# control_avr.net
KiCad netlist of a schematic drawn in EAGLE
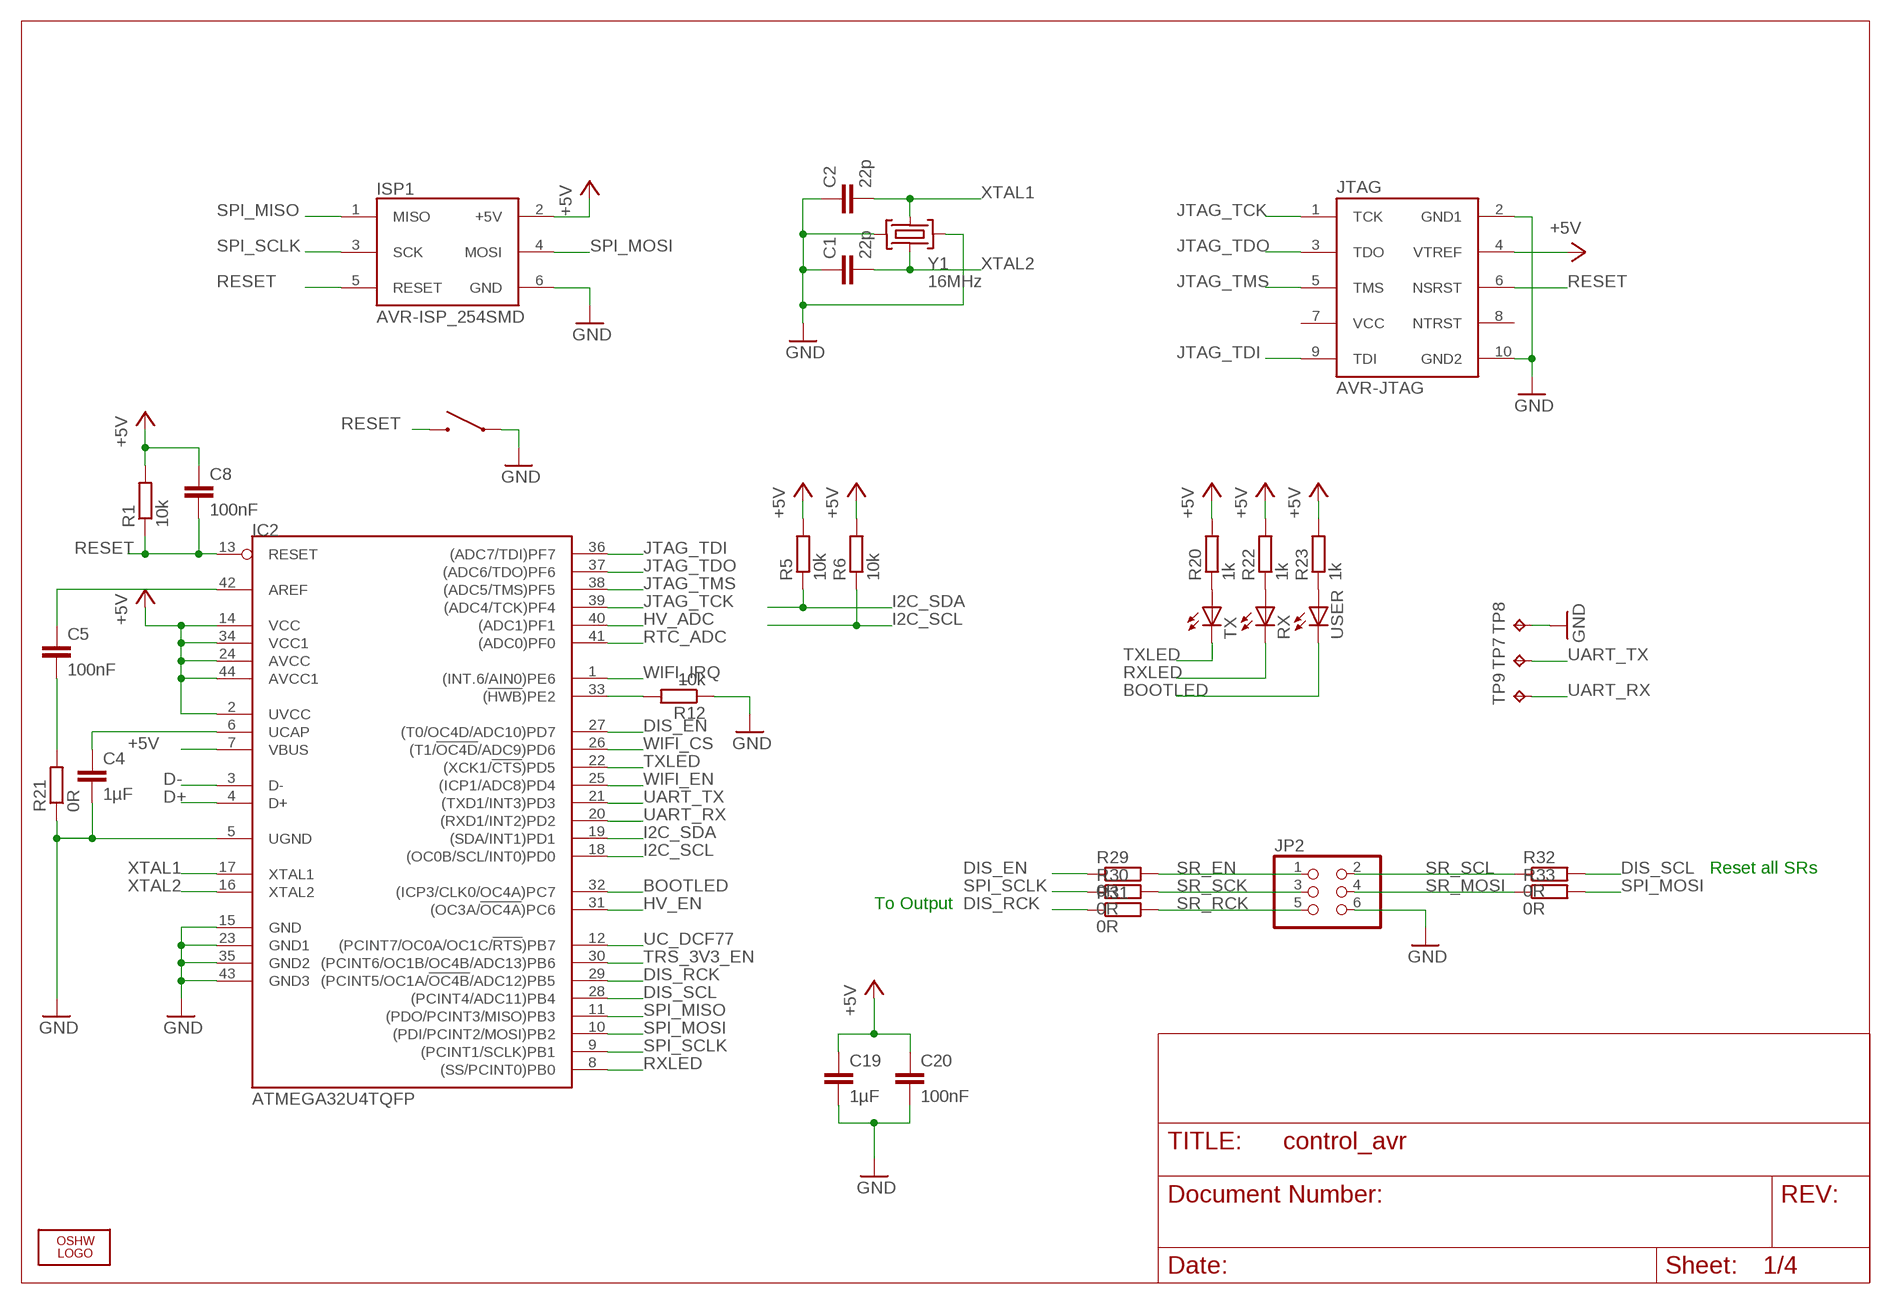
[diagram p0: schematic, sheet 1]
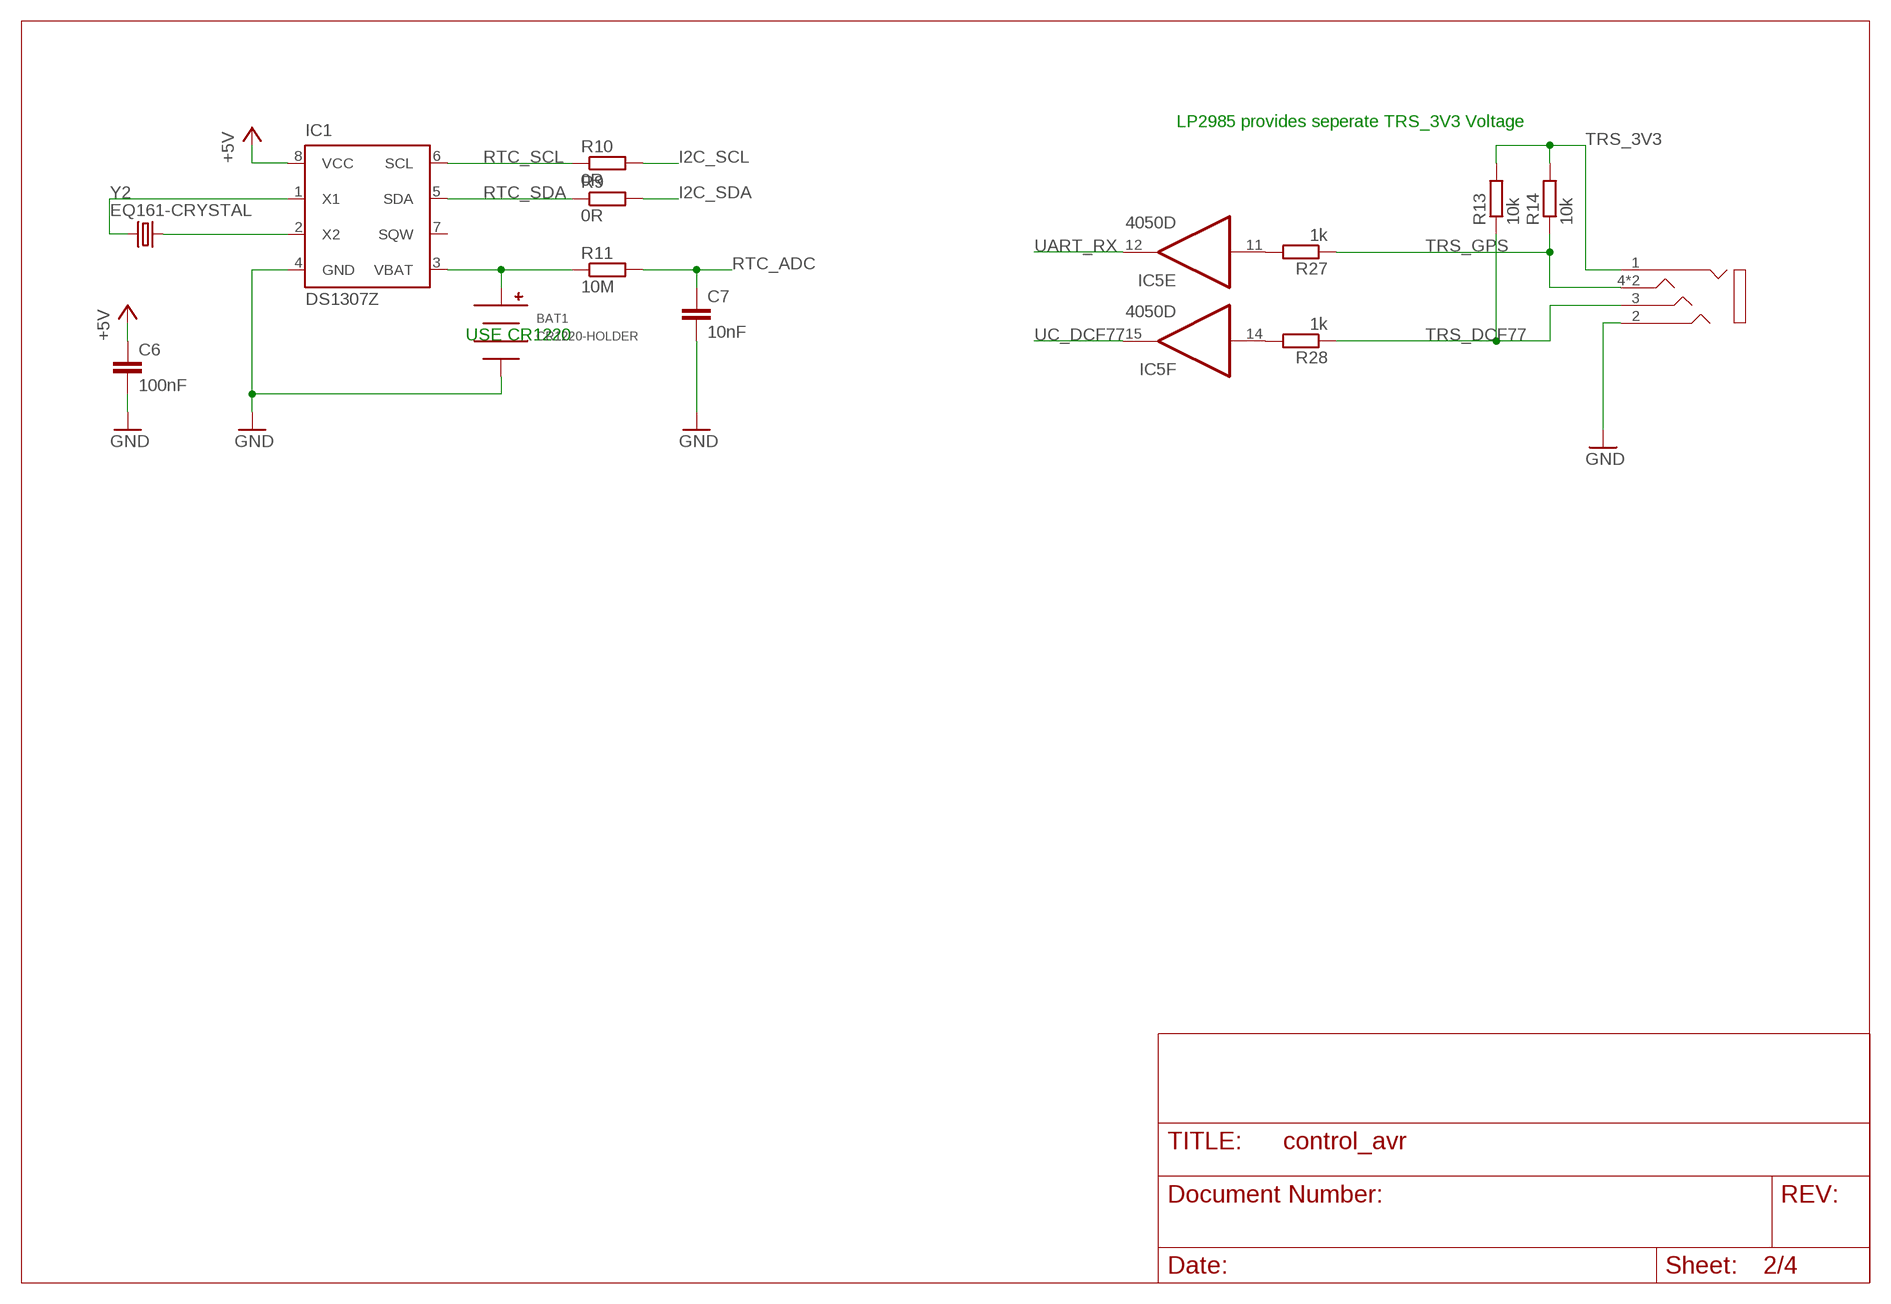
[diagram p1: schematic, sheet 2]
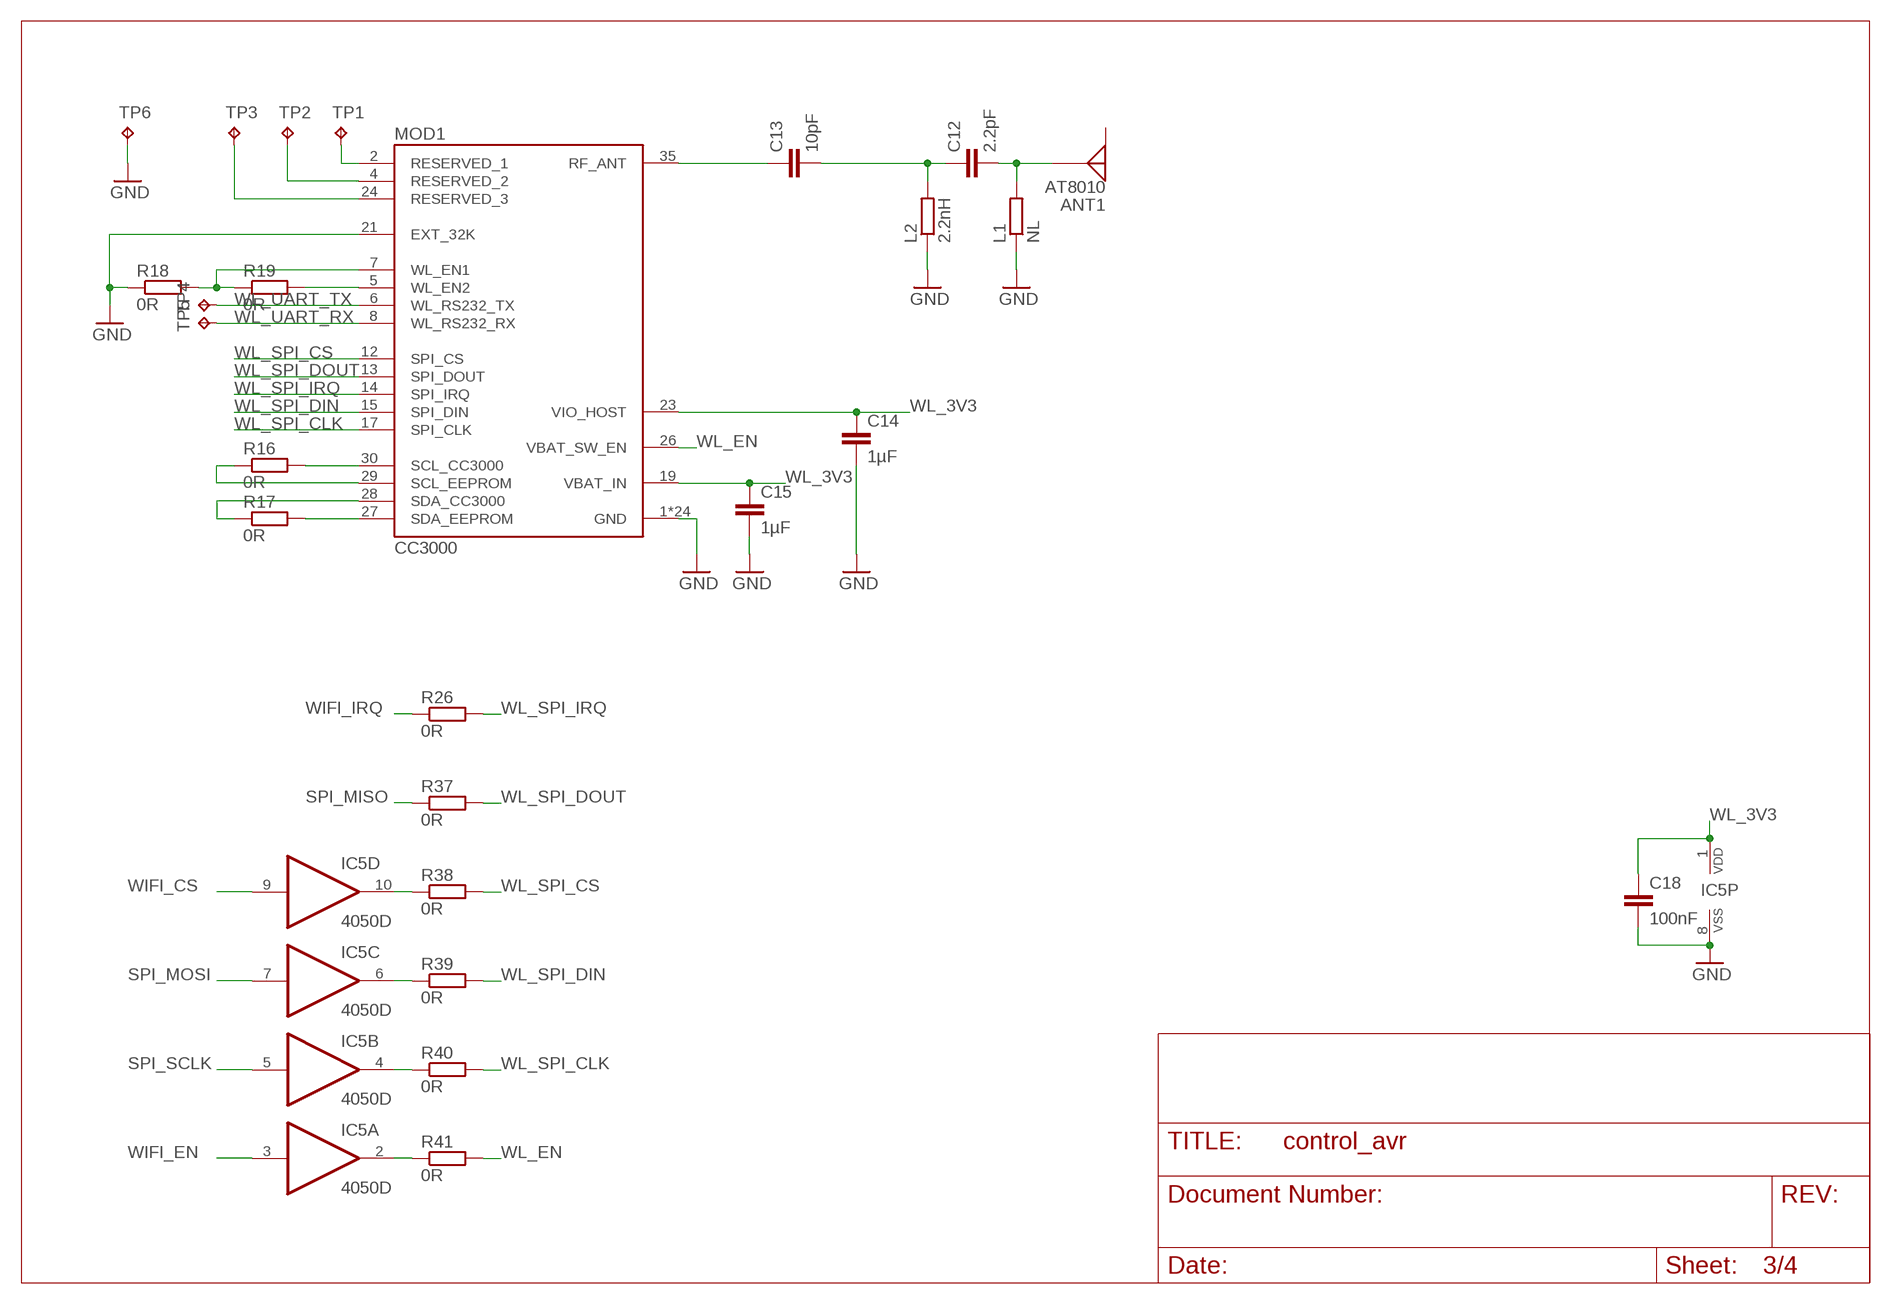
[diagram p2: schematic, sheet 3]
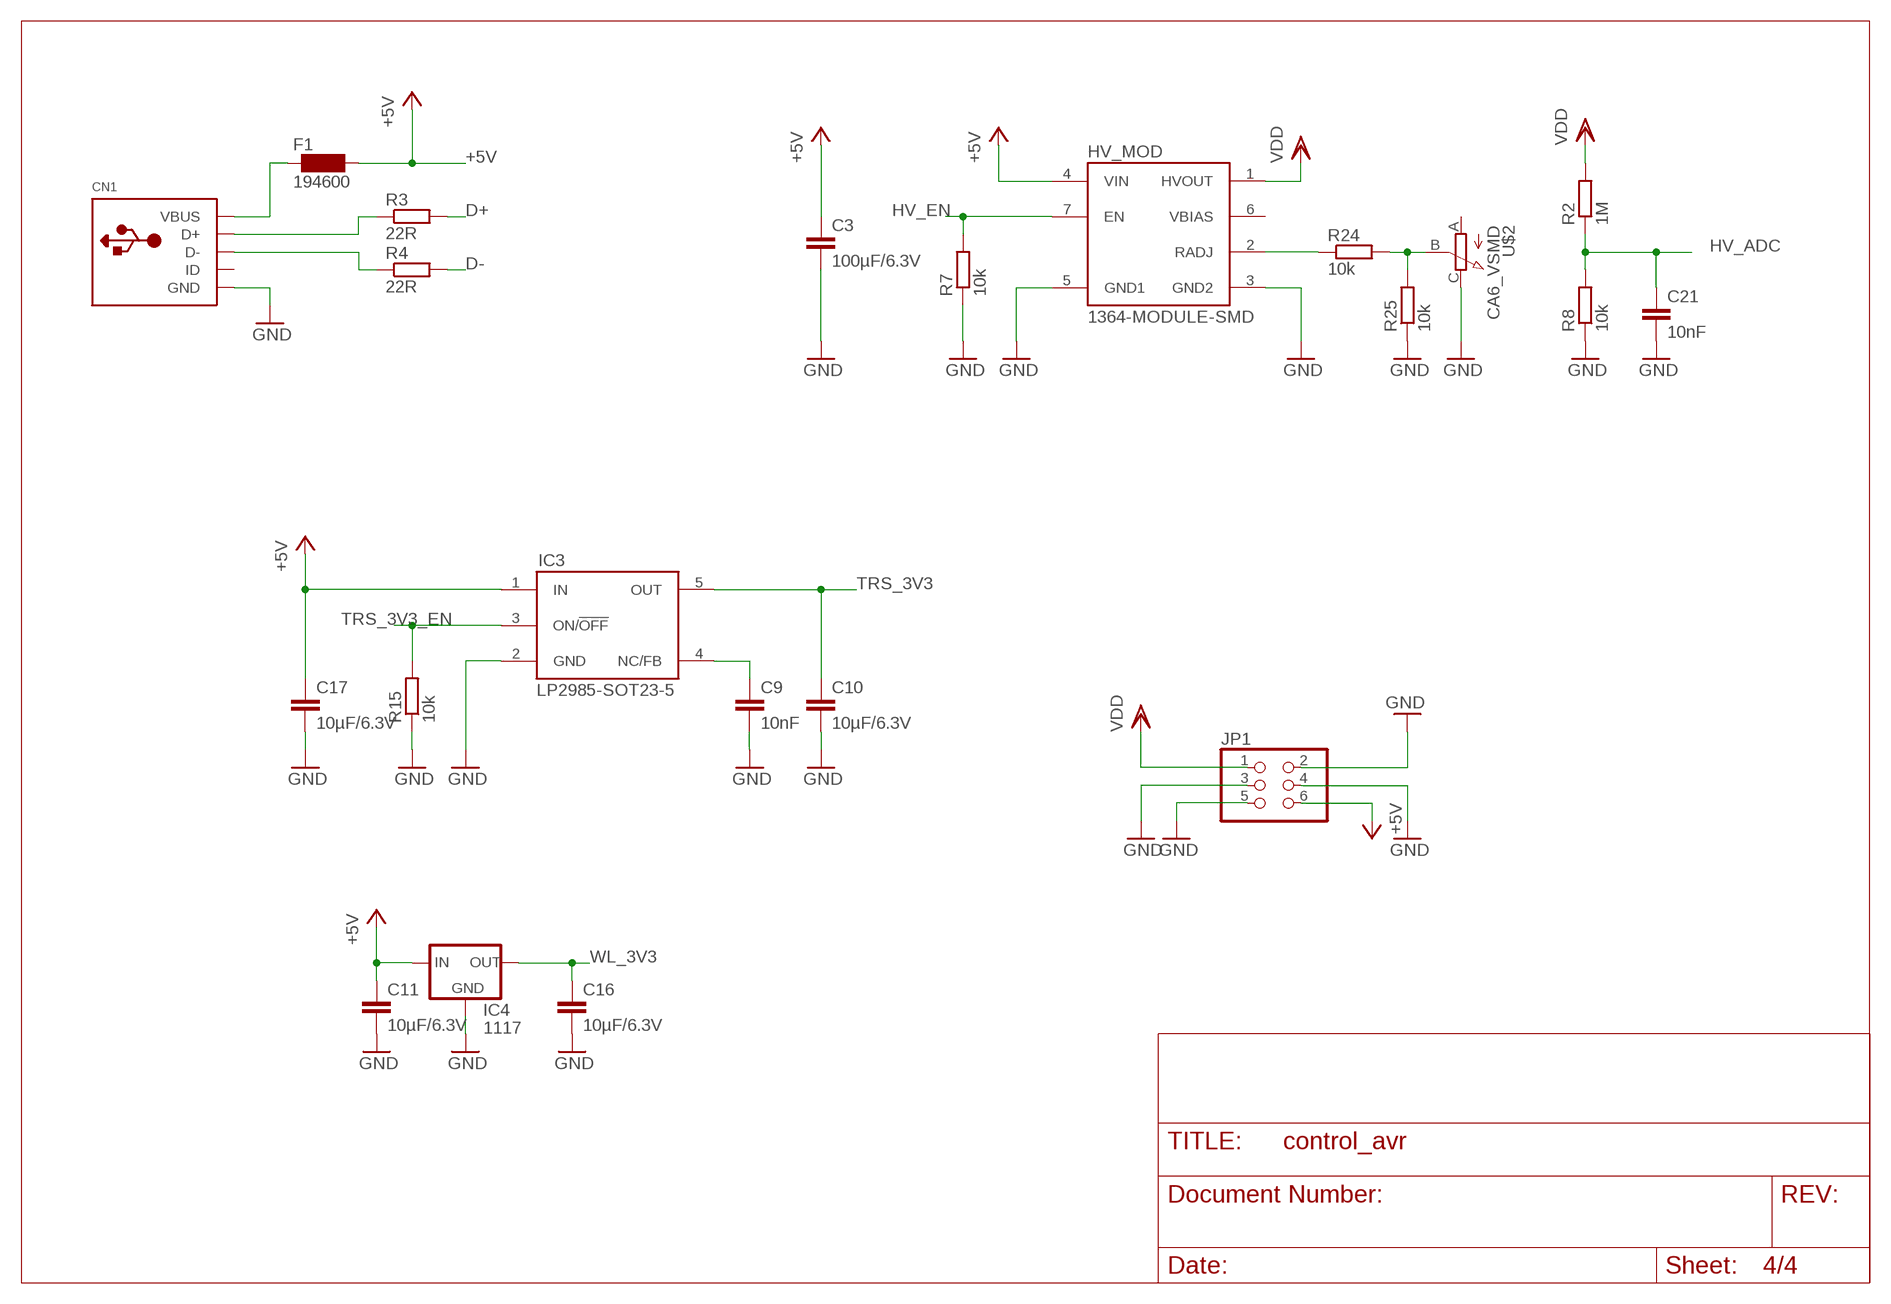
[diagram p3: schematic, sheet 4]

(export (version "E")
  (design (tool "Eeschema 10.0.6"))
  (components
    (comp (ref "ANT1")
      (value "AT8010")
      (footprint "eagle-import:AT8010")
      (libsource (lib "eagle-import") (part "AT8010"))
    )
    (comp (ref "C12")
      (value "2.2pF")
      (footprint "eagle-import:C0402")
      (libsource (lib "eagle-import") (part "C-EUC0402"))
    )
    (comp (ref "C13")
      (value "10pF")
      (footprint "eagle-import:C0402")
      (libsource (lib "eagle-import") (part "C-EUC0402"))
    )
    (comp (ref "C14")
      (value "1µF")
      (footprint "eagle-import:C0603")
      (libsource (lib "eagle-import") (part "C-EUC0603"))
    )
    (comp (ref "C15")
      (value "1µF")
      (footprint "eagle-import:C0603")
      (libsource (lib "eagle-import") (part "C-EUC0603"))
    )
    (comp (ref "C18")
      (value "100nF")
      (footprint "eagle-import:C0603")
      (libsource (lib "eagle-import") (part "C-EUC0603"))
    )
    (comp (ref "IC5")
      (value "4050D")
      (footprint "eagle-import:SO16")
      (libsource (lib "eagle-import") (part "4050D"))
    )
    (comp (ref "L1")
      (value "NL")
      (footprint "eagle-import:R0402")
      (libsource (lib "eagle-import") (part "R-EU_R0402"))
    )
    (comp (ref "L2")
      (value "2.2nH")
      (footprint "eagle-import:R0402")
      (libsource (lib "eagle-import") (part "R-EU_R0402"))
    )
    (comp (ref "MOD1")
      (value "CC3000")
      (footprint "eagle-import:CC3000")
      (libsource (lib "eagle-import") (part "CC3000"))
    )
    (comp (ref "R16")
      (value "0R")
      (footprint "eagle-import:R0603")
      (libsource (lib "eagle-import") (part "R-EU_R0603"))
    )
    (comp (ref "R17")
      (value "0R")
      (footprint "eagle-import:R0603")
      (libsource (lib "eagle-import") (part "R-EU_R0603"))
    )
    (comp (ref "R18")
      (value "0R")
      (footprint "eagle-import:R0603")
      (libsource (lib "eagle-import") (part "R-EU_R0603"))
    )
    (comp (ref "R19")
      (value "0R")
      (footprint "eagle-import:R0603")
      (libsource (lib "eagle-import") (part "R-EU_R0603"))
    )
    (comp (ref "R26")
      (value "0R")
      (footprint "eagle-import:R0603")
      (libsource (lib "eagle-import") (part "R-EU_R0603"))
    )
    (comp (ref "R37")
      (value "0R")
      (footprint "eagle-import:R0603")
      (libsource (lib "eagle-import") (part "R-EU_R0603"))
    )
    (comp (ref "R38")
      (value "0R")
      (footprint "eagle-import:R0603")
      (libsource (lib "eagle-import") (part "R-EU_R0603"))
    )
    (comp (ref "R39")
      (value "0R")
      (footprint "eagle-import:R0603")
      (libsource (lib "eagle-import") (part "R-EU_R0603"))
    )
    (comp (ref "R40")
      (value "0R")
      (footprint "eagle-import:R0603")
      (libsource (lib "eagle-import") (part "R-EU_R0603"))
    )
    (comp (ref "R41")
      (value "0R")
      (footprint "eagle-import:R0603")
      (libsource (lib "eagle-import") (part "R-EU_R0603"))
    )
    (comp (ref "TP1")
      (value "TPTP06R")
      (footprint "eagle-import:TP06R")
      (libsource (lib "eagle-import") (part "TPTP06R"))
    )
    (comp (ref "TP2")
      (value "TPTP06R")
      (footprint "eagle-import:TP06R")
      (libsource (lib "eagle-import") (part "TPTP06R"))
    )
    (comp (ref "TP3")
      (value "TPTP06R")
      (footprint "eagle-import:TP06R")
      (libsource (lib "eagle-import") (part "TPTP06R"))
    )
    (comp (ref "TP4")
      (value "TPTP10R")
      (footprint "eagle-import:TP10R")
      (libsource (lib "eagle-import") (part "TPTP10R"))
    )
    (comp (ref "TP5")
      (value "TPTP10R")
      (footprint "eagle-import:TP10R")
      (libsource (lib "eagle-import") (part "TPTP10R"))
    )
    (comp (ref "TP6")
      (value "TPTP10SQ")
      (footprint "eagle-import:TP10SQ")
      (libsource (lib "eagle-import") (part "TPTP10SQ"))
    )
    (comp (ref "C1")
      (value "22p")
      (footprint "eagle-import:C0603")
      (libsource (lib "eagle-import") (part "C-EUC0603"))
    )
    (comp (ref "C2")
      (value "22p")
      (footprint "eagle-import:C0603")
      (libsource (lib "eagle-import") (part "C-EUC0603"))
    )
    (comp (ref "C4")
      (value "1µF")
      (footprint "eagle-import:C0603")
      (libsource (lib "eagle-import") (part "C-EUC0603"))
    )
    (comp (ref "C5")
      (value "100nF")
      (footprint "eagle-import:C0603")
      (libsource (lib "eagle-import") (part "C-EUC0603"))
    )
    (comp (ref "C8")
      (value "100nF")
      (footprint "eagle-import:C0603")
      (libsource (lib "eagle-import") (part "C-EUC0603"))
    )
    (comp (ref "C19")
      (value "1µF")
      (footprint "eagle-import:C0603")
      (libsource (lib "eagle-import") (part "C-EUC0603"))
    )
    (comp (ref "C20")
      (value "100nF")
      (footprint "eagle-import:C0603")
      (libsource (lib "eagle-import") (part "C-EUC0603"))
    )
    (comp (ref "IC2")
      (value "ATMEGA32U4TQFP")
      (footprint "eagle-import:TQFP44")
      (libsource (lib "eagle-import") (part "ATMEGA32U4TQFP"))
    )
    (comp (ref "ISP1")
      (value "AVR-ISP_254SMD")
      (footprint "eagle-import:2X03SMD")
      (libsource (lib "eagle-import") (part "AVR-ISP_254SMD"))
    )
    (comp (ref "JP2")
      (value "PINHD-2X3_2.54-SMD-R")
      (footprint "eagle-import:2X03SMD_R")
      (libsource (lib "eagle-import") (part "PINHD-2X3_2.54-SMD-R"))
    )
    (comp (ref "JTAG")
      (value "AVR-JTAG")
      (footprint "eagle-import:20021121-10010XXLF")
      (libsource (lib "eagle-import") (part "AVR-JTAG"))
    )
    (comp (ref "LOGO1")
      (value "OSHW_LOGO_FILLX0200-NT")
      (footprint "eagle-import:OSHW_FILLX200_NOTEXT")
      (libsource (lib "eagle-import") (part "OSHW_LOGO_FILLX0200-NT"))
    )
    (comp (ref "R1")
      (value "10k")
      (footprint "eagle-import:R0603")
      (libsource (lib "eagle-import") (part "R-EU_R0603"))
    )
    (comp (ref "R5")
      (value "10k")
      (footprint "eagle-import:R0603")
      (libsource (lib "eagle-import") (part "R-EU_R0603"))
    )
    (comp (ref "R6")
      (value "10k")
      (footprint "eagle-import:R0603")
      (libsource (lib "eagle-import") (part "R-EU_R0603"))
    )
    (comp (ref "R12")
      (value "10k")
      (footprint "eagle-import:R0603")
      (libsource (lib "eagle-import") (part "R-EU_R0603"))
    )
    (comp (ref "R20")
      (value "1k")
      (footprint "eagle-import:R0603")
      (libsource (lib "eagle-import") (part "R-EU_R0603"))
    )
    (comp (ref "R21")
      (value "0R")
      (footprint "eagle-import:R0603")
      (libsource (lib "eagle-import") (part "R-EU_R0603"))
    )
    (comp (ref "R22")
      (value "1k")
      (footprint "eagle-import:R0603")
      (libsource (lib "eagle-import") (part "R-EU_R0603"))
    )
    (comp (ref "R23")
      (value "1k")
      (footprint "eagle-import:R0603")
      (libsource (lib "eagle-import") (part "R-EU_R0603"))
    )
    (comp (ref "R29")
      (value "0R")
      (footprint "eagle-import:R0603")
      (libsource (lib "eagle-import") (part "R-EU_R0603"))
    )
    (comp (ref "R30")
      (value "0R")
      (footprint "eagle-import:R0603")
      (libsource (lib "eagle-import") (part "R-EU_R0603"))
    )
    (comp (ref "R31")
      (value "0R")
      (footprint "eagle-import:R0603")
      (libsource (lib "eagle-import") (part "R-EU_R0603"))
    )
    (comp (ref "R32")
      (value "0R")
      (footprint "eagle-import:R0603")
      (libsource (lib "eagle-import") (part "R-EU_R0603"))
    )
    (comp (ref "R33")
      (value "0R")
      (footprint "eagle-import:R0603")
      (libsource (lib "eagle-import") (part "R-EU_R0603"))
    )
    (comp (ref "RESET")
      (value "TACT-SWITCH-47-35")
      (footprint "eagle-import:47-35")
      (libsource (lib "eagle-import") (part "TACT-SWITCH-47-35"))
    )
    (comp (ref "RX")
      (value "LEDCHIP-LED0603")
      (footprint "eagle-import:CHIP-LED0603")
      (libsource (lib "eagle-import") (part "LEDCHIP-LED0603"))
    )
    (comp (ref "TP7")
      (value "TPTP10R")
      (footprint "eagle-import:TP10R")
      (libsource (lib "eagle-import") (part "TPTP10R"))
    )
    (comp (ref "TP8")
      (value "TPTP10SQ")
      (footprint "eagle-import:TP10SQ")
      (libsource (lib "eagle-import") (part "TPTP10SQ"))
    )
    (comp (ref "TP9")
      (value "TPTP10R")
      (footprint "eagle-import:TP10R")
      (libsource (lib "eagle-import") (part "TPTP10R"))
    )
    (comp (ref "TX")
      (value "LEDCHIP-LED0603")
      (footprint "eagle-import:CHIP-LED0603")
      (libsource (lib "eagle-import") (part "LEDCHIP-LED0603"))
    )
    (comp (ref "USER")
      (value "LEDCHIP-LED0603")
      (footprint "eagle-import:CHIP-LED0603")
      (libsource (lib "eagle-import") (part "LEDCHIP-LED0603"))
    )
    (comp (ref "Y1")
      (value "16MHz")
      (footprint "eagle-import:X22")
      (libsource (lib "eagle-import") (part "X22-CRYSTAL"))
    )
    (comp (ref "BAT1")
      (value "CR1220-HOLDER")
      (footprint "eagle-import:HARWIN-CR1220")
      (libsource (lib "eagle-import") (part "CR1220-HOLDER"))
    )
    (comp (ref "C6")
      (value "100nF")
      (footprint "eagle-import:C0603")
      (libsource (lib "eagle-import") (part "C-EUC0603"))
    )
    (comp (ref "C7")
      (value "10nF")
      (footprint "eagle-import:C0603")
      (libsource (lib "eagle-import") (part "C-EUC0603"))
    )
    (comp (ref "IC1")
      (value "DS1307Z")
      (footprint "eagle-import:SOIC8")
      (libsource (lib "eagle-import") (part "DS1307Z"))
    )
    (comp (ref "R9")
      (value "0R")
      (footprint "eagle-import:R0603")
      (libsource (lib "eagle-import") (part "R-EU_R0603"))
    )
    (comp (ref "R10")
      (value "0R")
      (footprint "eagle-import:R0603")
      (libsource (lib "eagle-import") (part "R-EU_R0603"))
    )
    (comp (ref "R11")
      (value "10M")
      (footprint "eagle-import:R0603")
      (libsource (lib "eagle-import") (part "R-EU_R0603"))
    )
    (comp (ref "R13")
      (value "10k")
      (footprint "eagle-import:R0603")
      (libsource (lib "eagle-import") (part "R-EU_R0603"))
    )
    (comp (ref "R14")
      (value "10k")
      (footprint "eagle-import:R0603")
      (libsource (lib "eagle-import") (part "R-EU_R0603"))
    )
    (comp (ref "R27")
      (value "1k")
      (footprint "eagle-import:R0603")
      (libsource (lib "eagle-import") (part "R-EU_R0603"))
    )
    (comp (ref "R28")
      (value "1k")
      (footprint "eagle-import:R0603")
      (libsource (lib "eagle-import") (part "R-EU_R0603"))
    )
    (comp (ref "U$3")
      (value "1503_13")
      (footprint "eagle-import:1503-03")
      (libsource (lib "eagle-import") (part "1503_13"))
    )
    (comp (ref "Y2")
      (value "EQ161-CRYSTAL")
      (footprint "eagle-import:EQ161")
      (libsource (lib "eagle-import") (part "EQ161-CRYSTAL"))
    )
    (comp (ref "C3")
      (value "100µF/6.3V")
      (footprint "eagle-import:C1210")
      (libsource (lib "eagle-import") (part "C-EUC1210"))
    )
    (comp (ref "C9")
      (value "10nF")
      (footprint "eagle-import:C0603")
      (libsource (lib "eagle-import") (part "C-EUC0603"))
    )
    (comp (ref "C10")
      (value "10µF/6.3V")
      (footprint "eagle-import:C0603")
      (libsource (lib "eagle-import") (part "C-EUC0603"))
    )
    (comp (ref "C11")
      (value "10µF/6.3V")
      (footprint "eagle-import:C0603")
      (libsource (lib "eagle-import") (part "C-EUC0603"))
    )
    (comp (ref "C16")
      (value "10µF/6.3V")
      (footprint "eagle-import:C0603")
      (libsource (lib "eagle-import") (part "C-EUC0603"))
    )
    (comp (ref "C17")
      (value "10µF/6.3V")
      (footprint "eagle-import:C0603")
      (libsource (lib "eagle-import") (part "C-EUC0603"))
    )
    (comp (ref "C21")
      (value "10nF")
      (footprint "eagle-import:C0603")
      (libsource (lib "eagle-import") (part "C-EUC0603"))
    )
    (comp (ref "CN1")
      (value "USBMINIB")
      (footprint "eagle-import:USB-MINIB")
      (libsource (lib "eagle-import") (part "USBMINIB"))
    )
    (comp (ref "F1")
      (value "194600")
      (footprint "eagle-import:1812")
      (libsource (lib "eagle-import") (part "194600"))
    )
    (comp (ref "HV_MOD")
      (value "1364-MODULE-SMD")
      (footprint "eagle-import:1364-SMD")
      (libsource (lib "eagle-import") (part "1364-MODULE-SMD"))
    )
    (comp (ref "IC3")
      (value "LP2985-SOT23-5")
      (footprint "eagle-import:SOT23-5")
      (libsource (lib "eagle-import") (part "LP2985-SOT23-5"))
    )
    (comp (ref "IC4")
      (value "1117")
      (footprint "eagle-import:SOT223")
      (libsource (lib "eagle-import") (part "1117"))
    )
    (comp (ref "JP1")
      (value "PINHD-2X3_2.54-SMD-R")
      (footprint "eagle-import:2X03SMD_R")
      (libsource (lib "eagle-import") (part "PINHD-2X3_2.54-SMD-R"))
    )
    (comp (ref "R2")
      (value "1M")
      (footprint "eagle-import:R1206")
      (libsource (lib "eagle-import") (part "R-EU_R1206"))
    )
    (comp (ref "R3")
      (value "22R")
      (footprint "eagle-import:R0603")
      (libsource (lib "eagle-import") (part "R-EU_R0603"))
    )
    (comp (ref "R4")
      (value "22R")
      (footprint "eagle-import:R0603")
      (libsource (lib "eagle-import") (part "R-EU_R0603"))
    )
    (comp (ref "R7")
      (value "10k")
      (footprint "eagle-import:R0603")
      (libsource (lib "eagle-import") (part "R-EU_R0603"))
    )
    (comp (ref "R8")
      (value "10k")
      (footprint "eagle-import:R0603")
      (libsource (lib "eagle-import") (part "R-EU_R0603"))
    )
    (comp (ref "R15")
      (value "10k")
      (footprint "eagle-import:R0603")
      (libsource (lib "eagle-import") (part "R-EU_R0603"))
    )
    (comp (ref "R24")
      (value "10k")
      (footprint "eagle-import:R0603")
      (libsource (lib "eagle-import") (part "R-EU_R0603"))
    )
    (comp (ref "R25")
      (value "10k")
      (footprint "eagle-import:R0603")
      (libsource (lib "eagle-import") (part "R-EU_R0603"))
    )
    (comp (ref "U$2")
      (value "CA6_VSMD")
      (footprint "eagle-import:CA6-VSMD")
      (libsource (lib "eagle-import") (part "CA6_VSMD"))
    )
  )
  (nets
    (net (code "1") (name "+5V") (class "Default")
      (node (ref "C11") (pin "1") (pinfunction "1_1") (pintype "passive"))
      (node (ref "C17") (pin "1") (pinfunction "1_1") (pintype "passive"))
      (node (ref "C19") (pin "1") (pinfunction "1_1") (pintype "passive"))
      (node (ref "C20") (pin "1") (pinfunction "1_1") (pintype "passive"))
      (node (ref "C3") (pin "1") (pinfunction "1_1") (pintype "passive"))
      (node (ref "C6") (pin "1") (pinfunction "1_1") (pintype "passive"))
      (node (ref "C8") (pin "1") (pinfunction "1_1") (pintype "passive"))
      (node (ref "F1") (pin "P$2") (pinfunction "P$2_P$2") (pintype "bidirectional"))
      (node (ref "HV_MOD") (pin "4") (pinfunction "VIN_4") (pintype "bidirectional"))
      (node (ref "IC1") (pin "8") (pinfunction "VCC_8") (pintype "power_in"))
      (node (ref "IC2") (pin "14") (pinfunction "VCC_14") (pintype "bidirectional"))
      (node (ref "IC2") (pin "2") (pinfunction "UVCC_2") (pintype "bidirectional"))
      (node (ref "IC2") (pin "24") (pinfunction "AVCC_24") (pintype "bidirectional"))
      (node (ref "IC2") (pin "34") (pinfunction "VCC1_34") (pintype "bidirectional"))
      (node (ref "IC2") (pin "44") (pinfunction "AVCC1_44") (pintype "bidirectional"))
      (node (ref "IC2") (pin "7") (pinfunction "VBUS_7") (pintype "bidirectional"))
      (node (ref "IC3") (pin "1") (pinfunction "IN_1") (pintype "bidirectional"))
      (node (ref "IC4") (pin "3") (pinfunction "IN_3") (pintype "input"))
      (node (ref "ISP1") (pin "2") (pinfunction "+5V_2") (pintype "bidirectional"))
      (node (ref "JP1") (pin "6") (pinfunction "6_6") (pintype "passive"))
      (node (ref "JTAG") (pin "4") (pinfunction "VTREF_4") (pintype "bidirectional"))
      (node (ref "R1") (pin "2") (pinfunction "2_2") (pintype "passive"))
      (node (ref "R20") (pin "2") (pinfunction "2_2") (pintype "passive"))
      (node (ref "R22") (pin "2") (pinfunction "2_2") (pintype "passive"))
      (node (ref "R23") (pin "2") (pinfunction "2_2") (pintype "passive"))
      (node (ref "R5") (pin "2") (pinfunction "2_2") (pintype "passive"))
      (node (ref "R6") (pin "2") (pinfunction "2_2") (pintype "passive"))
    )
    (net (code "2") (name "BOOTLED") (class "Default")
      (node (ref "IC2") (pin "32") (pinfunction "(ICP3/CLK0/OC4A)PC7_32") (pintype "bidirectional"))
      (node (ref "USER") (pin "C") (pinfunction "C_C") (pintype "passive"))
    )
    (net (code "3") (name "D+") (class "Default")
      (node (ref "IC2") (pin "4") (pinfunction "D+_4") (pintype "bidirectional"))
      (node (ref "R3") (pin "2") (pinfunction "2_2") (pintype "passive"))
    )
    (net (code "4") (name "D-") (class "Default")
      (node (ref "IC2") (pin "3") (pinfunction "D-_3") (pintype "bidirectional"))
      (node (ref "R4") (pin "2") (pinfunction "2_2") (pintype "passive"))
    )
    (net (code "5") (name "DIS_EN") (class "Default")
      (node (ref "IC2") (pin "27") (pinfunction "(T0/OC4D/ADC10)PD7_27") (pintype "bidirectional"))
      (node (ref "R29") (pin "1") (pinfunction "1_1") (pintype "passive"))
    )
    (net (code "6") (name "DIS_RCK") (class "Default")
      (node (ref "IC2") (pin "29") (pinfunction "(PCINT5/OC1A/~{OC4B}/ADC12)PB5_29") (pintype "bidirectional"))
      (node (ref "R31") (pin "1") (pinfunction "1_1") (pintype "passive"))
    )
    (net (code "7") (name "DIS_SCL") (class "Default")
      (node (ref "IC2") (pin "28") (pinfunction "(PCINT4/ADC11)PB4_28") (pintype "bidirectional"))
      (node (ref "R32") (pin "2") (pinfunction "2_2") (pintype "passive"))
    )
    (net (code "8") (name "GND") (class "Default")
      (node (ref "BAT1") (pin "NEG") (pinfunction "NEG_NEG") (pintype "bidirectional"))
      (node (ref "C1") (pin "1") (pinfunction "1_1") (pintype "passive"))
      (node (ref "C10") (pin "2") (pinfunction "2_2") (pintype "passive"))
      (node (ref "C11") (pin "2") (pinfunction "2_2") (pintype "passive"))
      (node (ref "C14") (pin "2") (pinfunction "2_2") (pintype "passive"))
      (node (ref "C15") (pin "2") (pinfunction "2_2") (pintype "passive"))
      (node (ref "C16") (pin "2") (pinfunction "2_2") (pintype "passive"))
      (node (ref "C17") (pin "2") (pinfunction "2_2") (pintype "passive"))
      (node (ref "C18") (pin "2") (pinfunction "2_2") (pintype "passive"))
      (node (ref "C19") (pin "2") (pinfunction "2_2") (pintype "passive"))
      (node (ref "C2") (pin "1") (pinfunction "1_1") (pintype "passive"))
      (node (ref "C20") (pin "2") (pinfunction "2_2") (pintype "passive"))
      (node (ref "C21") (pin "2") (pinfunction "2_2") (pintype "passive"))
      (node (ref "C3") (pin "2") (pinfunction "2_2") (pintype "passive"))
      (node (ref "C4") (pin "2") (pinfunction "2_2") (pintype "passive"))
      (node (ref "C6") (pin "2") (pinfunction "2_2") (pintype "passive"))
      (node (ref "C7") (pin "2") (pinfunction "2_2") (pintype "passive"))
      (node (ref "C9") (pin "2") (pinfunction "2_2") (pintype "passive"))
      (node (ref "CN1") (pin "GND") (pinfunction "GND_GND") (pintype "power_in"))
      (node (ref "HV_MOD") (pin "3") (pinfunction "GND2_3") (pintype "bidirectional"))
      (node (ref "HV_MOD") (pin "5") (pinfunction "GND1_5") (pintype "bidirectional"))
      (node (ref "IC1") (pin "4") (pinfunction "GND_4") (pintype "power_in"))
      (node (ref "IC2") (pin "15") (pinfunction "GND_15") (pintype "bidirectional"))
      (node (ref "IC2") (pin "23") (pinfunction "GND1_23") (pintype "bidirectional"))
      (node (ref "IC2") (pin "35") (pinfunction "GND2_35") (pintype "bidirectional"))
      (node (ref "IC2") (pin "43") (pinfunction "GND3_43") (pintype "bidirectional"))
      (node (ref "IC2") (pin "5") (pinfunction "UGND_5") (pintype "bidirectional"))
      (node (ref "IC3") (pin "2") (pinfunction "GND_2") (pintype "bidirectional"))
      (node (ref "IC4") (pin "1") (pinfunction "GND_1") (pintype "input"))
      (node (ref "IC5") (pin "8") (pinfunction "VSS_8") (pintype "power_in"))
      (node (ref "ISP1") (pin "6") (pinfunction "GND_6") (pintype "bidirectional"))
      (node (ref "JP1") (pin "2") (pinfunction "2_2") (pintype "passive"))
      (node (ref "JP1") (pin "3") (pinfunction "3_3") (pintype "passive"))
      (node (ref "JP1") (pin "4") (pinfunction "4_4") (pintype "passive"))
      (node (ref "JP1") (pin "5") (pinfunction "5_5") (pintype "passive"))
      (node (ref "JP2") (pin "6") (pinfunction "6_6") (pintype "passive"))
      (node (ref "JTAG") (pin "10") (pinfunction "GND2_10") (pintype "bidirectional"))
      (node (ref "JTAG") (pin "2") (pinfunction "GND1_2") (pintype "bidirectional"))
      (node (ref "L1") (pin "1") (pinfunction "1_1") (pintype "passive"))
      (node (ref "L2") (pin "1") (pinfunction "1_1") (pintype "passive"))
      (node (ref "MOD1") (pin "1") (pinfunction "GND_1") (pintype "bidirectional"))
      (node (ref "MOD1") (pin "10") (pinfunction "GND_10") (pintype "bidirectional"))
      (node (ref "MOD1") (pin "11") (pinfunction "GND_11") (pintype "bidirectional"))
      (node (ref "MOD1") (pin "16") (pinfunction "GND_16") (pintype "bidirectional"))
      (node (ref "MOD1") (pin "18") (pinfunction "GND_18") (pintype "bidirectional"))
      (node (ref "MOD1") (pin "20") (pinfunction "GND_20") (pintype "bidirectional"))
      (node (ref "MOD1") (pin "21") (pinfunction "EXT_32K_21") (pintype "bidirectional"))
      (node (ref "MOD1") (pin "22") (pinfunction "GND_22") (pintype "bidirectional"))
      (node (ref "MOD1") (pin "25") (pinfunction "GND_25") (pintype "bidirectional"))
      (node (ref "MOD1") (pin "31") (pinfunction "GND_31") (pintype "bidirectional"))
      (node (ref "MOD1") (pin "32") (pinfunction "GND_32") (pintype "bidirectional"))
      (node (ref "MOD1") (pin "33") (pinfunction "GND_33") (pintype "bidirectional"))
      (node (ref "MOD1") (pin "34") (pinfunction "GND_34") (pintype "bidirectional"))
      (node (ref "MOD1") (pin "36") (pinfunction "GND_36") (pintype "bidirectional"))
      (node (ref "MOD1") (pin "37") (pinfunction "GND_37") (pintype "bidirectional"))
      (node (ref "MOD1") (pin "38") (pinfunction "GND_38") (pintype "bidirectional"))
      (node (ref "MOD1") (pin "39") (pinfunction "GND_39") (pintype "bidirectional"))
      (node (ref "MOD1") (pin "40") (pinfunction "GND_40") (pintype "bidirectional"))
      (node (ref "MOD1") (pin "41") (pinfunction "GND_41") (pintype "bidirectional"))
      (node (ref "MOD1") (pin "42") (pinfunction "GND_42") (pintype "bidirectional"))
      (node (ref "MOD1") (pin "43") (pinfunction "GND_43") (pintype "bidirectional"))
      (node (ref "MOD1") (pin "44") (pinfunction "GND_44") (pintype "bidirectional"))
      (node (ref "MOD1") (pin "45") (pinfunction "GND_45") (pintype "bidirectional"))
      (node (ref "MOD1") (pin "46") (pinfunction "GND_46") (pintype "bidirectional"))
      (node (ref "MOD1") (pin "9") (pinfunction "GND_9") (pintype "bidirectional"))
      (node (ref "R12") (pin "1") (pinfunction "1_1") (pintype "passive"))
      (node (ref "R15") (pin "1") (pinfunction "1_1") (pintype "passive"))
      (node (ref "R18") (pin "1") (pinfunction "1_1") (pintype "passive"))
      (node (ref "R21") (pin "1") (pinfunction "1_1") (pintype "passive"))
      (node (ref "R25") (pin "1") (pinfunction "1_1") (pintype "passive"))
      (node (ref "R7") (pin "1") (pinfunction "1_1") (pintype "passive"))
      (node (ref "R8") (pin "1") (pinfunction "1_1") (pintype "passive"))
      (node (ref "RESET") (pin "C") (pinfunction "P$2_C") (pintype "bidirectional"))
      (node (ref "RESET") (pin "D") (pinfunction "P$2_D") (pintype "bidirectional"))
      (node (ref "TP6") (pin "TP") (pinfunction "TP_TP") (pintype "input"))
      (node (ref "TP8") (pin "TP") (pinfunction "TP_TP") (pintype "input"))
      (node (ref "U$2") (pin "C") (pinfunction "E_C") (pintype "passive"))
      (node (ref "U$3") (pin "2") (pinfunction "2_2") (pintype "bidirectional"))
      (node (ref "Y1") (pin "P$1") (pinfunction "GND1_P$1") (pintype "bidirectional"))
      (node (ref "Y1") (pin "P$3") (pinfunction "GND2_P$3") (pintype "bidirectional"))
    )
    (net (code "9") (name "HV_ADC") (class "Default")
      (node (ref "C21") (pin "1") (pinfunction "1_1") (pintype "passive"))
      (node (ref "IC2") (pin "40") (pinfunction "(ADC1)PF1_40") (pintype "bidirectional"))
      (node (ref "R2") (pin "1") (pinfunction "1_1") (pintype "passive"))
      (node (ref "R8") (pin "2") (pinfunction "2_2") (pintype "passive"))
    )
    (net (code "10") (name "HV_EN") (class "Default")
      (node (ref "HV_MOD") (pin "7") (pinfunction "EN_7") (pintype "bidirectional"))
      (node (ref "IC2") (pin "31") (pinfunction "(OC3A/~{OC4A})PC6_31") (pintype "bidirectional"))
      (node (ref "R7") (pin "2") (pinfunction "2_2") (pintype "passive"))
    )
    (net (code "11") (name "I2C_SCL") (class "Default")
      (node (ref "IC2") (pin "18") (pinfunction "(OC0B/SCL/INT0)PD0_18") (pintype "bidirectional"))
      (node (ref "R10") (pin "2") (pinfunction "2_2") (pintype "passive"))
      (node (ref "R6") (pin "1") (pinfunction "1_1") (pintype "passive"))
    )
    (net (code "12") (name "I2C_SDA") (class "Default")
      (node (ref "IC2") (pin "19") (pinfunction "(SDA/INT1)PD1_19") (pintype "bidirectional"))
      (node (ref "R5") (pin "1") (pinfunction "1_1") (pintype "passive"))
      (node (ref "R9") (pin "2") (pinfunction "2_2") (pintype "passive"))
    )
    (net (code "13") (name "JTAG_TCK") (class "Default")
      (node (ref "IC2") (pin "39") (pinfunction "(ADC4/TCK)PF4_39") (pintype "bidirectional"))
      (node (ref "JTAG") (pin "1") (pinfunction "TCK_1") (pintype "bidirectional"))
    )
    (net (code "14") (name "JTAG_TDI") (class "Default")
      (node (ref "IC2") (pin "36") (pinfunction "(ADC7/TDI)PF7_36") (pintype "bidirectional"))
      (node (ref "JTAG") (pin "9") (pinfunction "TDI_9") (pintype "bidirectional"))
    )
    (net (code "15") (name "JTAG_TDO") (class "Default")
      (node (ref "IC2") (pin "37") (pinfunction "(ADC6/TDO)PF6_37") (pintype "bidirectional"))
      (node (ref "JTAG") (pin "3") (pinfunction "TDO_3") (pintype "bidirectional"))
    )
    (net (code "16") (name "JTAG_TMS") (class "Default")
      (node (ref "IC2") (pin "38") (pinfunction "(ADC5/TMS)PF5_38") (pintype "bidirectional"))
      (node (ref "JTAG") (pin "5") (pinfunction "TMS_5") (pintype "bidirectional"))
    )
    (net (code "17") (name "Net-(ANT1-PadANT)") (class "Default")
      (node (ref "ANT1") (pin "ANT") (pinfunction "ANT_ANT") (pintype "bidirectional"))
      (node (ref "C12") (pin "2") (pinfunction "2_2") (pintype "passive"))
      (node (ref "L1") (pin "2") (pinfunction "2_2") (pintype "passive"))
    )
    (net (code "18") (name "Net-(C5-Pad2)") (class "Default")
      (node (ref "C5") (pin "2") (pinfunction "2_2") (pintype "passive"))
      (node (ref "R21") (pin "2") (pinfunction "2_2") (pintype "passive"))
    )
    (net (code "19") (name "Net-(C12-Pad1)") (class "Default")
      (node (ref "C12") (pin "1") (pinfunction "1_1") (pintype "passive"))
      (node (ref "C13") (pin "2") (pinfunction "2_2") (pintype "passive"))
      (node (ref "L2") (pin "2") (pinfunction "2_2") (pintype "passive"))
    )
    (net (code "20") (name "Net-(CN1-PadD+)") (class "Default")
      (node (ref "CN1") (pin "D+") (pinfunction "D+_D+") (pintype "bidirectional"))
      (node (ref "R3") (pin "1") (pinfunction "1_1") (pintype "passive"))
    )
    (net (code "21") (name "Net-(CN1-PadD-)") (class "Default")
      (node (ref "CN1") (pin "D-") (pinfunction "D-_D-") (pintype "bidirectional"))
      (node (ref "R4") (pin "1") (pinfunction "1_1") (pintype "passive"))
    )
    (net (code "22") (name "Net-(CN1-PadVBUS)") (class "Default")
      (node (ref "CN1") (pin "VBUS") (pinfunction "VBUS_VBUS") (pintype "power_in"))
      (node (ref "F1") (pin "P$1") (pinfunction "P$1_P$1") (pintype "bidirectional"))
    )
    (net (code "23") (name "Net-(HV_MOD-RADJ)") (class "Default")
      (node (ref "HV_MOD") (pin "2") (pinfunction "RADJ_2") (pintype "bidirectional"))
      (node (ref "R24") (pin "1") (pinfunction "1_1") (pintype "passive"))
    )
    (net (code "24") (name "Net-(IC1-VBAT)") (class "Default")
      (node (ref "BAT1") (pin "POS") (pinfunction "POS_POS") (pintype "bidirectional"))
      (node (ref "IC1") (pin "3") (pinfunction "VBAT_3") (pintype "passive"))
      (node (ref "R11") (pin "1") (pinfunction "1_1") (pintype "passive"))
    )
    (net (code "25") (name "Net-(IC1-X1)") (class "Default")
      (node (ref "IC1") (pin "1") (pinfunction "X1_1") (pintype "input"))
      (node (ref "Y2") (pin "P$2") (pinfunction "2_P$2") (pintype "passive"))
    )
    (net (code "26") (name "Net-(IC1-X2)") (class "Default")
      (node (ref "IC1") (pin "2") (pinfunction "X2_2") (pintype "output"))
      (node (ref "Y2") (pin "P$1") (pinfunction "1_P$1") (pintype "passive"))
    )
    (net (code "27") (name "Net-(IC2-(~{HWB})PE2)") (class "Default")
      (node (ref "IC2") (pin "33") (pinfunction "(~{HWB})PE2_33") (pintype "bidirectional"))
      (node (ref "R12") (pin "2") (pinfunction "2_2") (pintype "passive"))
    )
    (net (code "28") (name "Net-(IC2-AREF)") (class "Default")
      (node (ref "C5") (pin "1") (pinfunction "1_1") (pintype "passive"))
      (node (ref "IC2") (pin "42") (pinfunction "AREF_42") (pintype "bidirectional"))
    )
    (net (code "29") (name "Net-(IC2-UCAP)") (class "Default")
      (node (ref "C4") (pin "1") (pinfunction "1_1") (pintype "passive"))
      (node (ref "IC2") (pin "6") (pinfunction "UCAP_6") (pintype "bidirectional"))
    )
    (net (code "30") (name "Net-(IC3-NC{slash}FB)") (class "Default")
      (node (ref "C9") (pin "1") (pinfunction "1_1") (pintype "passive"))
      (node (ref "IC3") (pin "4") (pinfunction "NC/FB_4") (pintype "bidirectional"))
    )
    (net (code "31") (name "Net-(IC5A-O)") (class "Default")
      (node (ref "IC5") (pin "2") (pinfunction "O_2") (pintype "output"))
      (node (ref "R41") (pin "1") (pinfunction "1_1") (pintype "passive"))
    )
    (net (code "32") (name "Net-(IC5B-O)") (class "Default")
      (node (ref "IC5") (pin "4") (pinfunction "O_4") (pintype "output"))
      (node (ref "R40") (pin "1") (pinfunction "1_1") (pintype "passive"))
    )
    (net (code "33") (name "Net-(IC5C-O)") (class "Default")
      (node (ref "IC5") (pin "6") (pinfunction "O_6") (pintype "output"))
      (node (ref "R39") (pin "1") (pinfunction "1_1") (pintype "passive"))
    )
    (net (code "34") (name "Net-(IC5D-O)") (class "Default")
      (node (ref "IC5") (pin "10") (pinfunction "O_10") (pintype "output"))
      (node (ref "R38") (pin "1") (pinfunction "1_1") (pintype "passive"))
    )
    (net (code "35") (name "Net-(IC5E-I)") (class "Default")
      (node (ref "IC5") (pin "11") (pinfunction "I_11") (pintype "input"))
      (node (ref "R27") (pin "2") (pinfunction "2_2") (pintype "passive"))
    )
    (net (code "36") (name "Net-(IC5F-I)") (class "Default")
      (node (ref "IC5") (pin "14") (pinfunction "I_14") (pintype "input"))
      (node (ref "R28") (pin "2") (pinfunction "2_2") (pintype "passive"))
    )
    (net (code "37") (name "Net-(MOD1-RESERVED_1)") (class "Default")
      (node (ref "MOD1") (pin "2") (pinfunction "RESERVED_1_2") (pintype "bidirectional"))
      (node (ref "TP1") (pin "TP") (pinfunction "TP_TP") (pintype "input"))
    )
    (net (code "38") (name "Net-(MOD1-RESERVED_2)") (class "Default")
      (node (ref "MOD1") (pin "4") (pinfunction "RESERVED_2_4") (pintype "bidirectional"))
      (node (ref "TP2") (pin "TP") (pinfunction "TP_TP") (pintype "input"))
    )
    (net (code "39") (name "Net-(MOD1-RESERVED_3)") (class "Default")
      (node (ref "MOD1") (pin "24") (pinfunction "RESERVED_3_24") (pintype "bidirectional"))
      (node (ref "TP3") (pin "TP") (pinfunction "TP_TP") (pintype "input"))
    )
    (net (code "40") (name "Net-(MOD1-RF_ANT)") (class "Default")
      (node (ref "C13") (pin "1") (pinfunction "1_1") (pintype "passive"))
      (node (ref "MOD1") (pin "35") (pinfunction "RF_ANT_35") (pintype "bidirectional"))
    )
    (net (code "41") (name "Net-(MOD1-SCL_CC3000)") (class "Default")
      (node (ref "MOD1") (pin "30") (pinfunction "SCL_CC3000_30") (pintype "bidirectional"))
      (node (ref "R16") (pin "2") (pinfunction "2_2") (pintype "passive"))
    )
    (net (code "42") (name "Net-(MOD1-SCL_EEPROM)") (class "Default")
      (node (ref "MOD1") (pin "29") (pinfunction "SCL_EEPROM_29") (pintype "bidirectional"))
      (node (ref "R16") (pin "1") (pinfunction "1_1") (pintype "passive"))
    )
    (net (code "43") (name "Net-(MOD1-SDA_CC3000)") (class "Default")
      (node (ref "MOD1") (pin "28") (pinfunction "SDA_CC3000_28") (pintype "bidirectional"))
      (node (ref "R17") (pin "1") (pinfunction "1_1") (pintype "passive"))
    )
    (net (code "44") (name "Net-(MOD1-SDA_EEPROM)") (class "Default")
      (node (ref "MOD1") (pin "27") (pinfunction "SDA_EEPROM_27") (pintype "bidirectional"))
      (node (ref "R17") (pin "2") (pinfunction "2_2") (pintype "passive"))
    )
    (net (code "45") (name "Net-(MOD1-WL_EN1)") (class "Default")
      (node (ref "MOD1") (pin "7") (pinfunction "WL_EN1_7") (pintype "bidirectional"))
      (node (ref "R18") (pin "2") (pinfunction "2_2") (pintype "passive"))
      (node (ref "R19") (pin "1") (pinfunction "1_1") (pintype "passive"))
    )
    (net (code "46") (name "Net-(MOD1-WL_EN2)") (class "Default")
      (node (ref "MOD1") (pin "5") (pinfunction "WL_EN2_5") (pintype "bidirectional"))
      (node (ref "R19") (pin "2") (pinfunction "2_2") (pintype "passive"))
    )
    (net (code "47") (name "Net-(R20-Pad1)") (class "Default")
      (node (ref "R20") (pin "1") (pinfunction "1_1") (pintype "passive"))
      (node (ref "TX") (pin "A") (pinfunction "A_A") (pintype "passive"))
    )
    (net (code "48") (name "Net-(R22-Pad1)") (class "Default")
      (node (ref "R22") (pin "1") (pinfunction "1_1") (pintype "passive"))
      (node (ref "RX") (pin "A") (pinfunction "A_A") (pintype "passive"))
    )
    (net (code "49") (name "Net-(R23-Pad1)") (class "Default")
      (node (ref "R23") (pin "1") (pinfunction "1_1") (pintype "passive"))
      (node (ref "USER") (pin "A") (pinfunction "A_A") (pintype "passive"))
    )
    (net (code "50") (name "Net-(U$2-S)") (class "Default")
      (node (ref "R24") (pin "2") (pinfunction "2_2") (pintype "passive"))
      (node (ref "R25") (pin "2") (pinfunction "2_2") (pintype "passive"))
      (node (ref "U$2") (pin "B") (pinfunction "S_B") (pintype "passive"))
    )
    (net (code "51") (name "RESET") (class "Default")
      (node (ref "C8") (pin "2") (pinfunction "2_2") (pintype "passive"))
      (node (ref "IC2") (pin "13") (pinfunction "RESET_13") (pintype "bidirectional"))
      (node (ref "ISP1") (pin "5") (pinfunction "RESET_5") (pintype "bidirectional"))
      (node (ref "JTAG") (pin "6") (pinfunction "NSRST_6") (pintype "bidirectional"))
      (node (ref "R1") (pin "1") (pinfunction "1_1") (pintype "passive"))
      (node (ref "RESET") (pin "A") (pinfunction "P$1_A") (pintype "bidirectional"))
      (node (ref "RESET") (pin "B") (pinfunction "P$1_B") (pintype "bidirectional"))
    )
    (net (code "52") (name "RTC_ADC") (class "Default")
      (node (ref "C7") (pin "1") (pinfunction "1_1") (pintype "passive"))
      (node (ref "IC2") (pin "41") (pinfunction "(ADC0)PF0_41") (pintype "bidirectional"))
      (node (ref "R11") (pin "2") (pinfunction "2_2") (pintype "passive"))
    )
    (net (code "53") (name "RTC_SCL") (class "Default")
      (node (ref "IC1") (pin "6") (pinfunction "SCL_6") (pintype "input"))
      (node (ref "R10") (pin "1") (pinfunction "1_1") (pintype "passive"))
    )
    (net (code "54") (name "RTC_SDA") (class "Default")
      (node (ref "IC1") (pin "5") (pinfunction "SDA_5") (pintype "bidirectional"))
      (node (ref "R9") (pin "1") (pinfunction "1_1") (pintype "passive"))
    )
    (net (code "55") (name "RXLED") (class "Default")
      (node (ref "IC2") (pin "8") (pinfunction "(SS/PCINT0)PB0_8") (pintype "bidirectional"))
      (node (ref "RX") (pin "C") (pinfunction "C_C") (pintype "passive"))
    )
    (net (code "56") (name "SPI_MISO") (class "Default")
      (node (ref "IC2") (pin "11") (pinfunction "(PDO/PCINT3/MISO)PB3_11") (pintype "bidirectional"))
      (node (ref "ISP1") (pin "1") (pinfunction "MISO_1") (pintype "bidirectional"))
      (node (ref "R37") (pin "1") (pinfunction "1_1") (pintype "passive"))
    )
    (net (code "57") (name "SPI_MOSI") (class "Default")
      (node (ref "IC2") (pin "10") (pinfunction "(PDI/PCINT2/MOSI)PB2_10") (pintype "bidirectional"))
      (node (ref "IC5") (pin "7") (pinfunction "I_7") (pintype "input"))
      (node (ref "ISP1") (pin "4") (pinfunction "MOSI_4") (pintype "bidirectional"))
      (node (ref "R33") (pin "2") (pinfunction "2_2") (pintype "passive"))
    )
    (net (code "58") (name "SPI_SCLK") (class "Default")
      (node (ref "IC2") (pin "9") (pinfunction "(PCINT1/SCLK)PB1_9") (pintype "bidirectional"))
      (node (ref "IC5") (pin "5") (pinfunction "I_5") (pintype "input"))
      (node (ref "ISP1") (pin "3") (pinfunction "SCK_3") (pintype "bidirectional"))
      (node (ref "R30") (pin "1") (pinfunction "1_1") (pintype "passive"))
    )
    (net (code "59") (name "SR_EN") (class "Default")
      (node (ref "JP2") (pin "1") (pinfunction "1_1") (pintype "passive"))
      (node (ref "R29") (pin "2") (pinfunction "2_2") (pintype "passive"))
    )
    (net (code "60") (name "SR_MOSI") (class "Default")
      (node (ref "JP2") (pin "4") (pinfunction "4_4") (pintype "passive"))
      (node (ref "R33") (pin "1") (pinfunction "1_1") (pintype "passive"))
    )
    (net (code "61") (name "SR_RCK") (class "Default")
      (node (ref "JP2") (pin "5") (pinfunction "5_5") (pintype "passive"))
      (node (ref "R31") (pin "2") (pinfunction "2_2") (pintype "passive"))
    )
    (net (code "62") (name "SR_SCK") (class "Default")
      (node (ref "JP2") (pin "3") (pinfunction "3_3") (pintype "passive"))
      (node (ref "R30") (pin "2") (pinfunction "2_2") (pintype "passive"))
    )
    (net (code "63") (name "SR_SCL") (class "Default")
      (node (ref "JP2") (pin "2") (pinfunction "2_2") (pintype "passive"))
      (node (ref "R32") (pin "1") (pinfunction "1_1") (pintype "passive"))
    )
    (net (code "64") (name "TRS_3V3") (class "Default")
      (node (ref "C10") (pin "1") (pinfunction "1_1") (pintype "passive"))
      (node (ref "IC3") (pin "5") (pinfunction "OUT_5") (pintype "bidirectional"))
      (node (ref "R13") (pin "2") (pinfunction "2_2") (pintype "passive"))
      (node (ref "R14") (pin "2") (pinfunction "2_2") (pintype "passive"))
      (node (ref "U$3") (pin "1") (pinfunction "1_1") (pintype "bidirectional"))
    )
    (net (code "65") (name "TRS_3V3_EN") (class "Default")
      (node (ref "IC2") (pin "30") (pinfunction "(PCINT6/OC1B/OC4B/ADC13)PB6_30") (pintype "bidirectional"))
      (node (ref "IC3") (pin "3") (pinfunction "ON/~{OFF}_3") (pintype "bidirectional"))
      (node (ref "R15") (pin "2") (pinfunction "2_2") (pintype "passive"))
    )
    (net (code "66") (name "TRS_DCF77") (class "Default")
      (node (ref "R13") (pin "1") (pinfunction "1_1") (pintype "passive"))
      (node (ref "R28") (pin "1") (pinfunction "1_1") (pintype "passive"))
      (node (ref "U$3") (pin "3") (pinfunction "3_3") (pintype "bidirectional"))
    )
    (net (code "67") (name "TRS_GPS") (class "Default")
      (node (ref "R14") (pin "1") (pinfunction "1_1") (pintype "passive"))
      (node (ref "R27") (pin "1") (pinfunction "1_1") (pintype "passive"))
      (node (ref "U$3") (pin "4") (pinfunction "4_4") (pintype "bidirectional"))
      (node (ref "U$3") (pin "4-2") (pinfunction "4_4-2") (pintype "bidirectional"))
    )
    (net (code "68") (name "TXLED") (class "Default")
      (node (ref "IC2") (pin "22") (pinfunction "(XCK1/~{CTS})PD5_22") (pintype "bidirectional"))
      (node (ref "TX") (pin "C") (pinfunction "C_C") (pintype "passive"))
    )
    (net (code "69") (name "UART_RX") (class "Default")
      (node (ref "IC2") (pin "20") (pinfunction "(RXD1/INT2)PD2_20") (pintype "bidirectional"))
      (node (ref "IC5") (pin "12") (pinfunction "O_12") (pintype "output"))
      (node (ref "TP9") (pin "TP") (pinfunction "TP_TP") (pintype "input"))
    )
    (net (code "70") (name "UART_TX") (class "Default")
      (node (ref "IC2") (pin "21") (pinfunction "(TXD1/INT3)PD3_21") (pintype "bidirectional"))
      (node (ref "TP7") (pin "TP") (pinfunction "TP_TP") (pintype "input"))
    )
    (net (code "71") (name "UC_DCF77") (class "Default")
      (node (ref "IC2") (pin "12") (pinfunction "(PCINT7/OC0A/OC1C/~{RTS})PB7_12") (pintype "bidirectional"))
      (node (ref "IC5") (pin "15") (pinfunction "O_15") (pintype "output"))
    )
    (net (code "72") (name "VDD") (class "Default")
      (node (ref "HV_MOD") (pin "1") (pinfunction "HVOUT_1") (pintype "bidirectional"))
      (node (ref "JP1") (pin "1") (pinfunction "1_1") (pintype "passive"))
      (node (ref "R2") (pin "2") (pinfunction "2_2") (pintype "passive"))
    )
    (net (code "73") (name "WIFI_CS") (class "Default")
      (node (ref "IC2") (pin "26") (pinfunction "(T1/~{OC4D}/ADC9)PD6_26") (pintype "bidirectional"))
      (node (ref "IC5") (pin "9") (pinfunction "I_9") (pintype "input"))
    )
    (net (code "74") (name "WIFI_EN") (class "Default")
      (node (ref "IC2") (pin "25") (pinfunction "(ICP1/ADC8)PD4_25") (pintype "bidirectional"))
      (node (ref "IC5") (pin "3") (pinfunction "I_3") (pintype "input"))
    )
    (net (code "75") (name "WIFI_IRQ") (class "Default")
      (node (ref "IC2") (pin "1") (pinfunction "(INT.6/AIN0)PE6_1") (pintype "bidirectional"))
      (node (ref "R26") (pin "1") (pinfunction "1_1") (pintype "passive"))
    )
    (net (code "76") (name "WL_3V3") (class "Default")
      (node (ref "C14") (pin "1") (pinfunction "1_1") (pintype "passive"))
      (node (ref "C15") (pin "1") (pinfunction "1_1") (pintype "passive"))
      (node (ref "C16") (pin "1") (pinfunction "1_1") (pintype "passive"))
      (node (ref "C18") (pin "1") (pinfunction "1_1") (pintype "passive"))
      (node (ref "IC4") (pin "2") (pinfunction "OUT_2") (pintype "passive"))
      (node (ref "IC4") (pin "4") (pinfunction "OUT_4") (pintype "passive"))
      (node (ref "IC5") (pin "1") (pinfunction "VDD_1") (pintype "power_in"))
      (node (ref "MOD1") (pin "19") (pinfunction "VBAT_IN_19") (pintype "bidirectional"))
      (node (ref "MOD1") (pin "23") (pinfunction "VIO_HOST_23") (pintype "bidirectional"))
    )
    (net (code "77") (name "WL_EN") (class "Default")
      (node (ref "MOD1") (pin "26") (pinfunction "VBAT_SW_EN_26") (pintype "bidirectional"))
      (node (ref "R41") (pin "2") (pinfunction "2_2") (pintype "passive"))
    )
    (net (code "78") (name "WL_SPI_CLK") (class "Default")
      (node (ref "MOD1") (pin "17") (pinfunction "SPI_CLK_17") (pintype "bidirectional"))
      (node (ref "R40") (pin "2") (pinfunction "2_2") (pintype "passive"))
    )
    (net (code "79") (name "WL_SPI_CS") (class "Default")
      (node (ref "MOD1") (pin "12") (pinfunction "SPI_CS_12") (pintype "bidirectional"))
      (node (ref "R38") (pin "2") (pinfunction "2_2") (pintype "passive"))
    )
    (net (code "80") (name "WL_SPI_DIN") (class "Default")
      (node (ref "MOD1") (pin "15") (pinfunction "SPI_DIN_15") (pintype "bidirectional"))
      (node (ref "R39") (pin "2") (pinfunction "2_2") (pintype "passive"))
    )
    (net (code "81") (name "WL_SPI_DOUT") (class "Default")
      (node (ref "MOD1") (pin "13") (pinfunction "SPI_DOUT_13") (pintype "bidirectional"))
      (node (ref "R37") (pin "2") (pinfunction "2_2") (pintype "passive"))
    )
    (net (code "82") (name "WL_SPI_IRQ") (class "Default")
      (node (ref "MOD1") (pin "14") (pinfunction "SPI_IRQ_14") (pintype "bidirectional"))
      (node (ref "R26") (pin "2") (pinfunction "2_2") (pintype "passive"))
    )
    (net (code "83") (name "WL_UART_RX") (class "Default")
      (node (ref "MOD1") (pin "8") (pinfunction "WL_RS232_RX_8") (pintype "bidirectional"))
      (node (ref "TP5") (pin "TP") (pinfunction "TP_TP") (pintype "input"))
    )
    (net (code "84") (name "WL_UART_TX") (class "Default")
      (node (ref "MOD1") (pin "6") (pinfunction "WL_RS232_TX_6") (pintype "bidirectional"))
      (node (ref "TP4") (pin "TP") (pinfunction "TP_TP") (pintype "input"))
    )
    (net (code "85") (name "XTAL1") (class "Default")
      (node (ref "C2") (pin "2") (pinfunction "2_2") (pintype "passive"))
      (node (ref "IC2") (pin "17") (pinfunction "XTAL1_17") (pintype "bidirectional"))
      (node (ref "Y1") (pin "CRYSTAL2") (pinfunction "CRYSTAL2_CRYSTAL2") (pintype "bidirectional"))
    )
    (net (code "86") (name "XTAL2") (class "Default")
      (node (ref "C1") (pin "2") (pinfunction "2_2") (pintype "passive"))
      (node (ref "IC2") (pin "16") (pinfunction "XTAL2_16") (pintype "bidirectional"))
      (node (ref "Y1") (pin "CRYSTAL1") (pinfunction "CRYSTAL1_CRYSTAL1") (pintype "bidirectional"))
    )
    (net (code "87") (name "unconnected-(ANT1-PadMOUNT)") (class "Default")
      (node (ref "ANT1") (pin "MOUNT") (pinfunction "MOUNT_MOUNT") (pintype "bidirectional"))
    )
    (net (code "88") (name "unconnected-(CN1-PadID)") (class "Default")
      (node (ref "CN1") (pin "ID") (pinfunction "ID_ID") (pintype "bidirectional"))
    )
    (net (code "89") (name "unconnected-(HV_MOD-VBIAS-Pad6)") (class "Default")
      (node (ref "HV_MOD") (pin "6") (pinfunction "VBIAS_6") (pintype "bidirectional"))
    )
    (net (code "90") (name "unconnected-(IC1-SQW-Pad7)") (class "Default")
      (node (ref "IC1") (pin "7") (pinfunction "SQW_7") (pintype "open_collector"))
    )
    (net (code "91") (name "unconnected-(JTAG-NTRST-Pad8)") (class "Default")
      (node (ref "JTAG") (pin "8") (pinfunction "NTRST_8") (pintype "bidirectional"))
    )
    (net (code "92") (name "unconnected-(JTAG-VCC-Pad7)") (class "Default")
      (node (ref "JTAG") (pin "7") (pinfunction "VCC_7") (pintype "bidirectional"))
    )
    (net (code "93") (name "unconnected-(U$2-PadA)") (class "Default")
      (node (ref "U$2") (pin "A") (pinfunction "A_A") (pintype "passive"))
    )
  )
)
